# Shee.net
KiCad netlist of a schematic drawn in Altium Designer
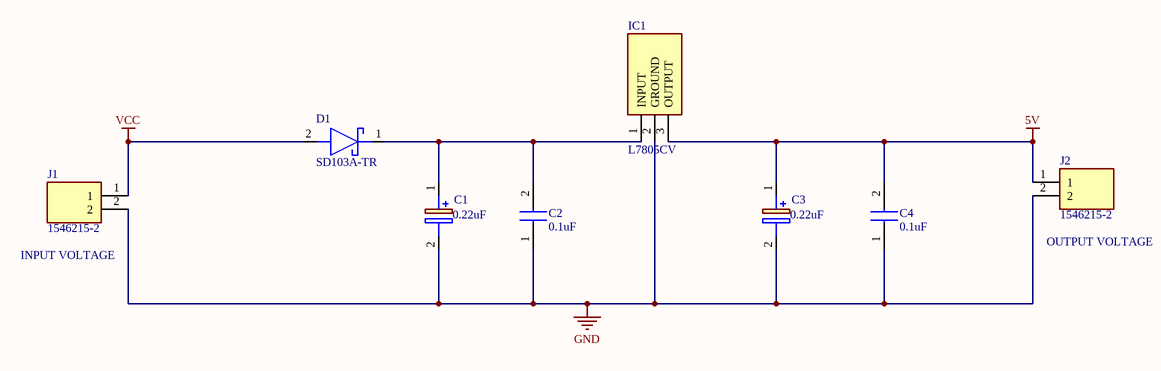
[diagram p0: Shee.SchDoc]

(export (version "E")
  (design (tool "Eeschema 10.0.6"))
  (components
    (comp (ref "C1")
      (value "0.22uF")
      (footprint "SamacSys:CAPPRD200W52D500H1250")
      (description "Capacitor Polarised")
      (fields
        (field (name "MANUFACTURER_PART_NUMBER") "860010772002")
        (field (name "MOUSER PART NUMBER") "710-860010772002")
      )
      (libsource (lib "*") (part "860010772002"))
    )
    (comp (ref "C2")
      (value "0.1uF")
      (footprint "SamacSys:RDER71E104K0P1H03B")
      (description "Capacitor")
      (fields
        (field (name "MANUFACTURER_PART_NUMBER") "RDER71E104K0P1H03B")
        (field (name "MOUSER PART NUMBER") "81-RDER71E104K0P1H3B")
      )
      (libsource (lib "*") (part "RDER71E104K0P1H03B"))
    )
    (comp (ref "C3")
      (value "0.22uF")
      (footprint "SamacSys:CAPPRD200W52D500H1250")
      (description "Capacitor Polarised")
      (fields
        (field (name "MANUFACTURER_PART_NUMBER") "860010772002")
        (field (name "MOUSER PART NUMBER") "710-860010772002")
      )
      (libsource (lib "*") (part "860010772002"))
    )
    (comp (ref "C4")
      (value "0.1uF")
      (footprint "SamacSys:RDER71E104K0P1H03B")
      (description "Capacitor")
      (fields
        (field (name "MANUFACTURER_PART_NUMBER") "RDER71E104K0P1H03B")
        (field (name "MOUSER PART NUMBER") "81-RDER71E104K0P1H3B")
      )
      (libsource (lib "*") (part "RDER71E104K0P1H03B"))
    )
    (comp (ref "D1")
      (value "SD103A-TR")
      (footprint "SamacSys:DIOAD950W60L350D150")
      (description "Schottky Diode")
      (fields (field (name "MOUSER PART NUMBER") "625-SD103A"))
      (libsource (lib "*") (part "SD103A-TR"))
    )
    (comp (ref "IC1")
      (value "L7805CV")
      (footprint "SamacSys:TO255P460X1020X2008-3P")
      (description "Integrated Circuit")
      (fields (field (name "MOUSER PART NUMBER") "511-L7805CV"))
      (libsource (lib "*") (part "L7805CV"))
    )
    (comp (ref "J1")
      (value "1546215-2")
      (footprint "SamacSys:15462152")
      (description "Connector")
      (fields (field (name "MOUSER PART NUMBER") "571-1546215-2"))
      (libsource (lib "*") (part "1546215-2"))
    )
    (comp (ref "J2")
      (value "1546215-2")
      (footprint "SamacSys:15462152")
      (description "Connector")
      (fields (field (name "MOUSER PART NUMBER") "571-1546215-2"))
      (libsource (lib "") (part "1546215-2_1"))
    )
  )
  (nets
    (net (code "1") (name "5V") (class "Default")
      (node (ref "C3") (pin "1") (pinfunction "+_1") (pintype "passive"))
      (node (ref "C4") (pin "2") (pinfunction "2_2") (pintype "passive"))
      (node (ref "IC1") (pin "3") (pinfunction "OUTPUT_3") (pintype "passive"))
      (node (ref "J2") (pin "1") (pinfunction "1_1") (pintype "passive"))
    )
    (net (code "2") (name "GND") (class "Default")
      (node (ref "C1") (pin "2") (pinfunction "-_2") (pintype "passive"))
      (node (ref "C2") (pin "1") (pinfunction "1_1") (pintype "passive"))
      (node (ref "C3") (pin "2") (pinfunction "-_2") (pintype "passive"))
      (node (ref "C4") (pin "1") (pinfunction "1_1") (pintype "passive"))
      (node (ref "IC1") (pin "2") (pinfunction "GROUND_2") (pintype "passive"))
      (node (ref "J1") (pin "2") (pinfunction "2_2") (pintype "passive"))
      (node (ref "J2") (pin "2") (pinfunction "2_2") (pintype "passive"))
    )
    (net (code "3") (name "Net-(C1-+)") (class "Default")
      (node (ref "C1") (pin "1") (pinfunction "+_1") (pintype "passive"))
      (node (ref "C2") (pin "2") (pinfunction "2_2") (pintype "passive"))
      (node (ref "D1") (pin "1") (pinfunction "K_1") (pintype "passive"))
      (node (ref "IC1") (pin "1") (pinfunction "INPUT_1") (pintype "passive"))
    )
    (net (code "4") (name "VCC") (class "Default")
      (node (ref "D1") (pin "2") (pinfunction "A_2") (pintype "passive"))
      (node (ref "J1") (pin "1") (pinfunction "1_1") (pintype "passive"))
    )
  )
)
